# CAN_Adapter.net
KiCad netlist of a schematic drawn in EAGLE
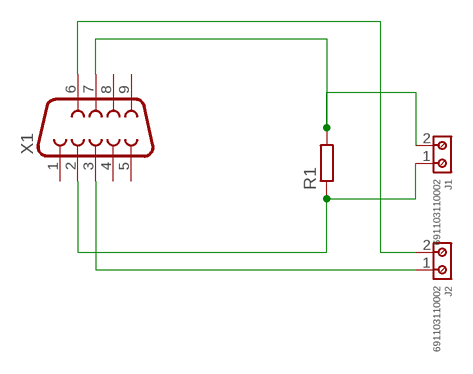
[diagram p0: schematic, sheet 1]

(export (version "E")
  (design (tool "Eeschema 10.0.6"))
  (components
    (comp (ref "J1")
      (value "691103110002")
      (footprint "eagle-import:691103110002")
      (libsource (lib "eagle-import") (part "691103110002"))
    )
    (comp (ref "J2")
      (value "691103110002")
      (footprint "eagle-import:691103110002")
      (libsource (lib "eagle-import") (part "691103110002"))
    )
    (comp (ref "R1")
      (value "R-EU_0204/7")
      (footprint "eagle-import:0204_7")
      (libsource (lib "eagle-import") (part "R-EU_0204/7"))
    )
    (comp (ref "X1")
      (value "F09D")
      (footprint "eagle-import:F09D")
      (libsource (lib "eagle-import") (part "F09D"))
    )
  )
  (nets
    (net (code "1") (name "Net-(J1-Pad1)") (class "Default")
      (node (ref "J1") (pin "1") (pinfunction "1_1") (pintype "passive"))
      (node (ref "R1") (pin "1") (pinfunction "1_1") (pintype "passive"))
      (node (ref "X1") (pin "2") (pinfunction "2_2") (pintype "passive"))
    )
    (net (code "2") (name "Net-(J1-Pad2)") (class "Default")
      (node (ref "J1") (pin "2") (pinfunction "2_2") (pintype "passive"))
      (node (ref "R1") (pin "2") (pinfunction "2_2") (pintype "passive"))
      (node (ref "X1") (pin "7") (pinfunction "7_7") (pintype "passive"))
    )
    (net (code "3") (name "Net-(J2-Pad1)") (class "Default")
      (node (ref "J2") (pin "1") (pinfunction "1_1") (pintype "passive"))
      (node (ref "X1") (pin "3") (pinfunction "3_3") (pintype "passive"))
    )
    (net (code "4") (name "Net-(J2-Pad2)") (class "Default")
      (node (ref "J2") (pin "2") (pinfunction "2_2") (pintype "passive"))
      (node (ref "X1") (pin "6") (pinfunction "6_6") (pintype "passive"))
    )
    (net (code "5") (name "unconnected-(X1-Pad1)") (class "Default")
      (node (ref "X1") (pin "1") (pinfunction "1_1") (pintype "passive"))
    )
    (net (code "6") (name "unconnected-(X1-Pad4)") (class "Default")
      (node (ref "X1") (pin "4") (pinfunction "4_4") (pintype "passive"))
    )
    (net (code "7") (name "unconnected-(X1-Pad5)") (class "Default")
      (node (ref "X1") (pin "5") (pinfunction "5_5") (pintype "passive"))
    )
    (net (code "8") (name "unconnected-(X1-Pad8)") (class "Default")
      (node (ref "X1") (pin "8") (pinfunction "8_8") (pintype "passive"))
    )
    (net (code "9") (name "unconnected-(X1-Pad9)") (class "Default")
      (node (ref "X1") (pin "9") (pinfunction "9_9") (pintype "passive"))
    )
  )
)
